# DIOT_SMA_Supply.net
KiCad netlist of a schematic drawn in Altium Designer
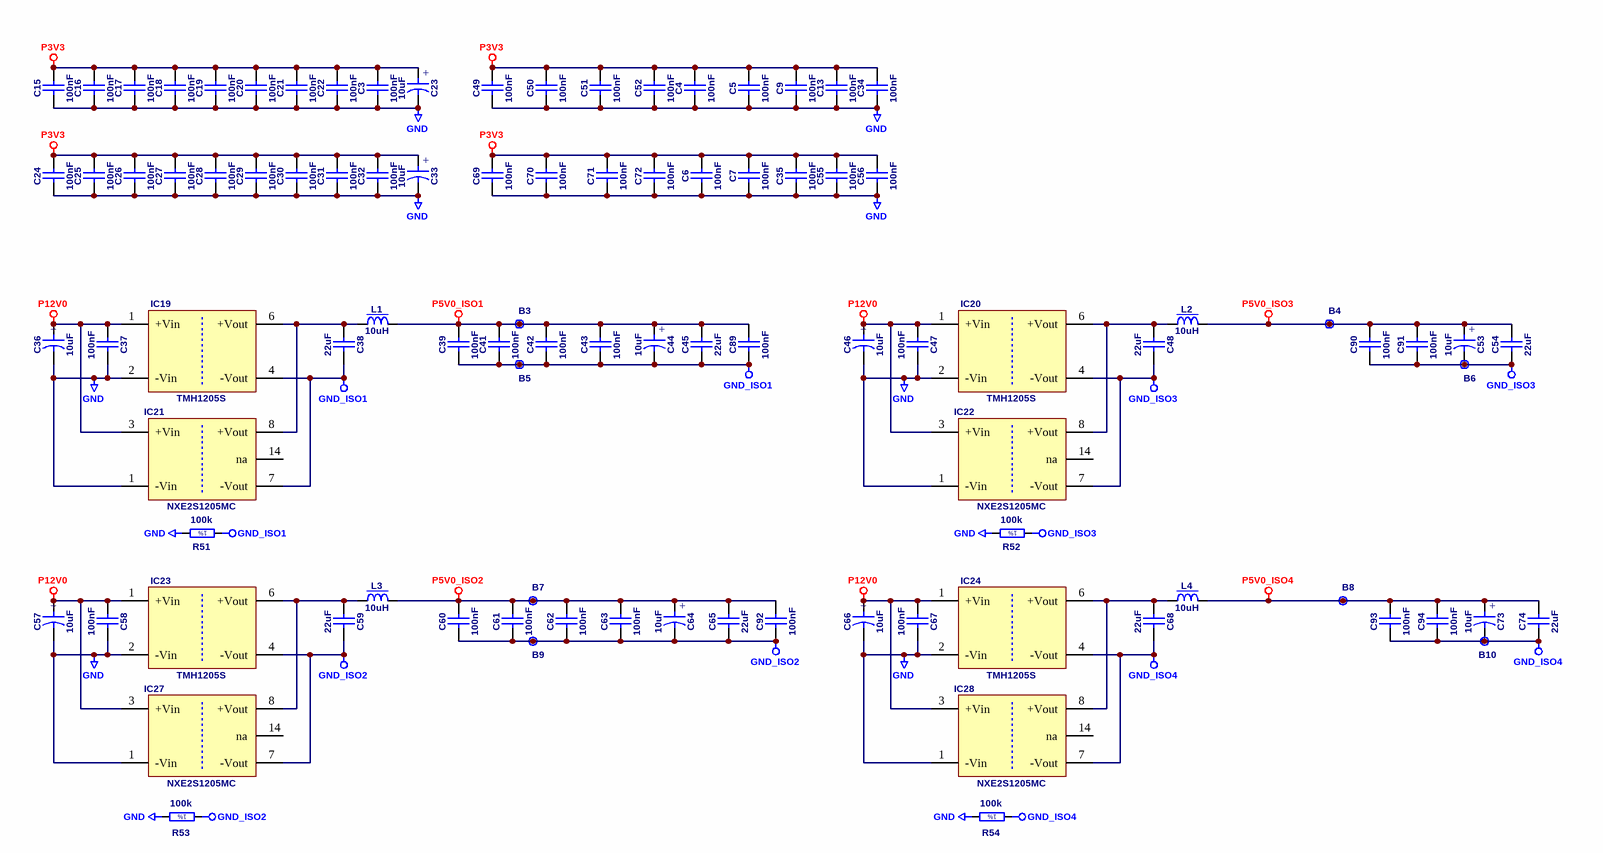
[diagram p0: DIOT_SMA_Supply.SchDoc]

(export (version "E")
  (design (tool "Eeschema 10.0.6"))
  (components
    (comp (ref "B3")
      (value "Plated Hole")
      (footprint "c130h60")
      (description "Single Terminal Socket")
      (fields (field (name "PART NUMBER") "PLATED_HOLE0.6_PAD1.3") (field (name "AUTHOR") "CERN DEM MR"))
      (libsource (lib "Eletro-mechanical") (part "Single Terminal Socket"))
    )
    (comp (ref "B4")
      (value "Plated Hole")
      (footprint "c130h60")
      (description "Single Terminal Socket")
      (fields (field (name "PART NUMBER") "PLATED_HOLE0.6_PAD1.3") (field (name "AUTHOR") "CERN DEM MR"))
      (libsource (lib "Eletro-mechanical") (part "Single Terminal Socket"))
    )
    (comp (ref "B5")
      (value "Plated Hole")
      (footprint "c130h60")
      (description "Single Terminal Socket")
      (fields (field (name "PART NUMBER") "PLATED_HOLE0.6_PAD1.3") (field (name "AUTHOR") "CERN DEM MR"))
      (libsource (lib "Eletro-mechanical") (part "Single Terminal Socket"))
    )
    (comp (ref "B6")
      (value "Plated Hole")
      (footprint "c130h60")
      (description "Single Terminal Socket")
      (fields (field (name "PART NUMBER") "PLATED_HOLE0.6_PAD1.3") (field (name "AUTHOR") "CERN DEM MR"))
      (libsource (lib "Eletro-mechanical") (part "Single Terminal Socket"))
    )
    (comp (ref "B7")
      (value "Plated Hole")
      (footprint "c130h60")
      (description "Single Terminal Socket")
      (fields (field (name "PART NUMBER") "PLATED_HOLE0.6_PAD1.3") (field (name "AUTHOR") "CERN DEM MR"))
      (libsource (lib "Eletro-mechanical") (part "Single Terminal Socket"))
    )
    (comp (ref "B8")
      (value "Plated Hole")
      (footprint "c130h60")
      (description "Single Terminal Socket")
      (fields (field (name "PART NUMBER") "PLATED_HOLE0.6_PAD1.3") (field (name "AUTHOR") "CERN DEM MR"))
      (libsource (lib "Eletro-mechanical") (part "Single Terminal Socket"))
    )
    (comp (ref "B9")
      (value "Plated Hole")
      (footprint "c130h60")
      (description "Single Terminal Socket")
      (fields (field (name "PART NUMBER") "PLATED_HOLE0.6_PAD1.3") (field (name "AUTHOR") "CERN DEM MR"))
      (libsource (lib "Eletro-mechanical") (part "Single Terminal Socket"))
    )
    (comp (ref "B10")
      (value "Plated Hole")
      (footprint "c130h60")
      (description "Single Terminal Socket")
      (fields (field (name "PART NUMBER") "PLATED_HOLE0.6_PAD1.3") (field (name "AUTHOR") "CERN DEM MR"))
      (libsource (lib "Eletro-mechanical") (part "Single Terminal Socket"))
    )
    (comp (ref "C3")
      (value "100nF")
      (footprint "CAPC1005X55N")
      (description "Non-polarised capacitor")
      (fields
        (field (name "PART NUMBER") "CC0402_100NF_16V_10%_X5R")
        (field (name "VOLTAGE") "16V")
        (field (name "AUTHOR") "CERN DEM JLC")
      )
      (libsource (lib "Capacitors") (part "Capacitor - non polarized"))
    )
    (comp (ref "C4")
      (value "100nF")
      (footprint "CAPC1005X55N")
      (description "Non-polarised capacitor")
      (fields
        (field (name "PART NUMBER") "CC0402_100NF_16V_10%_X5R")
        (field (name "VOLTAGE") "16V")
        (field (name "AUTHOR") "CERN DEM JLC")
      )
      (libsource (lib "Capacitors") (part "Capacitor - non polarized"))
    )
    (comp (ref "C5")
      (value "100nF")
      (footprint "CAPC1005X55N")
      (description "Non-polarised capacitor")
      (fields
        (field (name "PART NUMBER") "CC0402_100NF_16V_10%_X5R")
        (field (name "VOLTAGE") "16V")
        (field (name "AUTHOR") "CERN DEM JLC")
      )
      (libsource (lib "Capacitors") (part "Capacitor - non polarized"))
    )
    (comp (ref "C6")
      (value "100nF")
      (footprint "CAPC1005X55N")
      (description "Non-polarised capacitor")
      (fields
        (field (name "PART NUMBER") "CC0402_100NF_16V_10%_X5R")
        (field (name "VOLTAGE") "16V")
        (field (name "AUTHOR") "CERN DEM JLC")
      )
      (libsource (lib "Capacitors") (part "Capacitor - non polarized"))
    )
    (comp (ref "C7")
      (value "100nF")
      (footprint "CAPC1005X55N")
      (description "Non-polarised capacitor")
      (fields
        (field (name "PART NUMBER") "CC0402_100NF_16V_10%_X5R")
        (field (name "VOLTAGE") "16V")
        (field (name "AUTHOR") "CERN DEM JLC")
      )
      (libsource (lib "Capacitors") (part "Capacitor - non polarized"))
    )
    (comp (ref "C9")
      (value "100nF")
      (footprint "CAPC1005X55N")
      (description "Non-polarised capacitor")
      (fields
        (field (name "PART NUMBER") "CC0402_100NF_16V_10%_X5R")
        (field (name "VOLTAGE") "16V")
        (field (name "AUTHOR") "CERN DEM JLC")
      )
      (libsource (lib "Capacitors") (part "Capacitor - non polarized"))
    )
    (comp (ref "C13")
      (value "100nF")
      (footprint "CAPC1005X55N")
      (description "Non-polarised capacitor")
      (fields
        (field (name "PART NUMBER") "CC0402_100NF_16V_10%_X5R")
        (field (name "VOLTAGE") "16V")
        (field (name "AUTHOR") "CERN DEM JLC")
      )
      (libsource (lib "Capacitors") (part "Capacitor - non polarized"))
    )
    (comp (ref "C15")
      (value "100nF")
      (footprint "CAPC1005X55N")
      (description "Non-polarised capacitor")
      (fields
        (field (name "PART NUMBER") "CC0402_100NF_16V_10%_X5R")
        (field (name "VOLTAGE") "16V")
        (field (name "AUTHOR") "CERN DEM JLC")
      )
      (libsource (lib "Capacitors") (part "Capacitor - non polarized"))
    )
    (comp (ref "C16")
      (value "100nF")
      (footprint "CAPC1005X55N")
      (description "Non-polarised capacitor")
      (fields
        (field (name "PART NUMBER") "CC0402_100NF_16V_10%_X5R")
        (field (name "VOLTAGE") "16V")
        (field (name "AUTHOR") "CERN DEM JLC")
      )
      (libsource (lib "Capacitors") (part "Capacitor - non polarized"))
    )
    (comp (ref "C17")
      (value "100nF")
      (footprint "CAPC1005X55N")
      (description "Non-polarised capacitor")
      (fields
        (field (name "PART NUMBER") "CC0402_100NF_16V_10%_X5R")
        (field (name "VOLTAGE") "16V")
        (field (name "AUTHOR") "CERN DEM JLC")
      )
      (libsource (lib "Capacitors") (part "Capacitor - non polarized"))
    )
    (comp (ref "C18")
      (value "100nF")
      (footprint "CAPC1005X55N")
      (description "Non-polarised capacitor")
      (fields
        (field (name "PART NUMBER") "CC0402_100NF_16V_10%_X5R")
        (field (name "VOLTAGE") "16V")
        (field (name "AUTHOR") "CERN DEM JLC")
      )
      (libsource (lib "Capacitors") (part "Capacitor - non polarized"))
    )
    (comp (ref "C19")
      (value "100nF")
      (footprint "CAPC1005X55N")
      (description "Non-polarised capacitor")
      (fields
        (field (name "PART NUMBER") "CC0402_100NF_16V_10%_X5R")
        (field (name "VOLTAGE") "16V")
        (field (name "AUTHOR") "CERN DEM JLC")
      )
      (libsource (lib "Capacitors") (part "Capacitor - non polarized"))
    )
    (comp (ref "C20")
      (value "100nF")
      (footprint "CAPC1005X55N")
      (description "Non-polarised capacitor")
      (fields
        (field (name "PART NUMBER") "CC0402_100NF_16V_10%_X5R")
        (field (name "VOLTAGE") "16V")
        (field (name "AUTHOR") "CERN DEM JLC")
      )
      (libsource (lib "Capacitors") (part "Capacitor - non polarized"))
    )
    (comp (ref "C21")
      (value "100nF")
      (footprint "CAPC1005X55N")
      (description "Non-polarised capacitor")
      (fields
        (field (name "PART NUMBER") "CC0402_100NF_16V_10%_X5R")
        (field (name "VOLTAGE") "16V")
        (field (name "AUTHOR") "CERN DEM JLC")
      )
      (libsource (lib "Capacitors") (part "Capacitor - non polarized"))
    )
    (comp (ref "C22")
      (value "100nF")
      (footprint "CAPC1005X55N")
      (description "Non-polarised capacitor")
      (fields
        (field (name "PART NUMBER") "CC0402_100NF_16V_10%_X5R")
        (field (name "VOLTAGE") "16V")
        (field (name "AUTHOR") "CERN DEM JLC")
      )
      (libsource (lib "Capacitors") (part "Capacitor - non polarized"))
    )
    (comp (ref "C23")
      (value "10uF")
      (footprint "CAPAE430X540N")
      (description "Polarised capacitor")
      (fields
        (field (name "PART NUMBER") "CAE430-540_10UF_16V_20%")
        (field (name "VOLTAGE") "16V")
        (field (name "AUTHOR") "CERN DEM JLC")
      )
      (libsource (lib "Capacitors") (part "Capacitor - polarized"))
    )
    (comp (ref "C24")
      (value "100nF")
      (footprint "CAPC1005X55N")
      (description "Non-polarised capacitor")
      (fields
        (field (name "PART NUMBER") "CC0402_100NF_16V_10%_X5R")
        (field (name "VOLTAGE") "16V")
        (field (name "AUTHOR") "CERN DEM JLC")
      )
      (libsource (lib "Capacitors") (part "Capacitor - non polarized"))
    )
    (comp (ref "C25")
      (value "100nF")
      (footprint "CAPC1005X55N")
      (description "Non-polarised capacitor")
      (fields
        (field (name "PART NUMBER") "CC0402_100NF_16V_10%_X5R")
        (field (name "VOLTAGE") "16V")
        (field (name "AUTHOR") "CERN DEM JLC")
      )
      (libsource (lib "Capacitors") (part "Capacitor - non polarized"))
    )
    (comp (ref "C26")
      (value "100nF")
      (footprint "CAPC1005X55N")
      (description "Non-polarised capacitor")
      (fields
        (field (name "PART NUMBER") "CC0402_100NF_16V_10%_X5R")
        (field (name "VOLTAGE") "16V")
        (field (name "AUTHOR") "CERN DEM JLC")
      )
      (libsource (lib "Capacitors") (part "Capacitor - non polarized"))
    )
    (comp (ref "C27")
      (value "100nF")
      (footprint "CAPC1005X55N")
      (description "Non-polarised capacitor")
      (fields
        (field (name "PART NUMBER") "CC0402_100NF_16V_10%_X5R")
        (field (name "VOLTAGE") "16V")
        (field (name "AUTHOR") "CERN DEM JLC")
      )
      (libsource (lib "Capacitors") (part "Capacitor - non polarized"))
    )
    (comp (ref "C28")
      (value "100nF")
      (footprint "CAPC1005X55N")
      (description "Non-polarised capacitor")
      (fields
        (field (name "PART NUMBER") "CC0402_100NF_16V_10%_X5R")
        (field (name "VOLTAGE") "16V")
        (field (name "AUTHOR") "CERN DEM JLC")
      )
      (libsource (lib "Capacitors") (part "Capacitor - non polarized"))
    )
    (comp (ref "C29")
      (value "100nF")
      (footprint "CAPC1005X55N")
      (description "Non-polarised capacitor")
      (fields
        (field (name "PART NUMBER") "CC0402_100NF_16V_10%_X5R")
        (field (name "VOLTAGE") "16V")
        (field (name "AUTHOR") "CERN DEM JLC")
      )
      (libsource (lib "Capacitors") (part "Capacitor - non polarized"))
    )
    (comp (ref "C30")
      (value "100nF")
      (footprint "CAPC1005X55N")
      (description "Non-polarised capacitor")
      (fields
        (field (name "PART NUMBER") "CC0402_100NF_16V_10%_X5R")
        (field (name "VOLTAGE") "16V")
        (field (name "AUTHOR") "CERN DEM JLC")
      )
      (libsource (lib "Capacitors") (part "Capacitor - non polarized"))
    )
    (comp (ref "C31")
      (value "100nF")
      (footprint "CAPC1005X55N")
      (description "Non-polarised capacitor")
      (fields
        (field (name "PART NUMBER") "CC0402_100NF_16V_10%_X5R")
        (field (name "VOLTAGE") "16V")
        (field (name "AUTHOR") "CERN DEM JLC")
      )
      (libsource (lib "Capacitors") (part "Capacitor - non polarized"))
    )
    (comp (ref "C32")
      (value "100nF")
      (footprint "CAPC1005X55N")
      (description "Non-polarised capacitor")
      (fields
        (field (name "PART NUMBER") "CC0402_100NF_16V_10%_X5R")
        (field (name "VOLTAGE") "16V")
        (field (name "AUTHOR") "CERN DEM JLC")
      )
      (libsource (lib "Capacitors") (part "Capacitor - non polarized"))
    )
    (comp (ref "C33")
      (value "10uF")
      (footprint "CAPAE430X540N")
      (description "Polarised capacitor")
      (fields
        (field (name "PART NUMBER") "CAE430-540_10UF_16V_20%")
        (field (name "VOLTAGE") "16V")
        (field (name "AUTHOR") "CERN DEM JLC")
      )
      (libsource (lib "Capacitors") (part "Capacitor - polarized"))
    )
    (comp (ref "C34")
      (value "100nF")
      (footprint "CAPC1005X55N")
      (description "Non-polarised capacitor")
      (fields
        (field (name "PART NUMBER") "CC0402_100NF_16V_10%_X5R")
        (field (name "VOLTAGE") "16V")
        (field (name "AUTHOR") "CERN DEM JLC")
      )
      (libsource (lib "Capacitors") (part "Capacitor - non polarized"))
    )
    (comp (ref "C35")
      (value "100nF")
      (footprint "CAPC1005X55N")
      (description "Non-polarised capacitor")
      (fields
        (field (name "PART NUMBER") "CC0402_100NF_16V_10%_X5R")
        (field (name "VOLTAGE") "16V")
        (field (name "AUTHOR") "CERN DEM JLC")
      )
      (libsource (lib "Capacitors") (part "Capacitor - non polarized"))
    )
    (comp (ref "C36")
      (value "10uF")
      (footprint "CAPAE430X540N")
      (description "Polarised capacitor")
      (fields
        (field (name "PART NUMBER") "CAE430-540_10UF_16V_20%")
        (field (name "VOLTAGE") "16V")
        (field (name "AUTHOR") "CERN DEM JLC")
      )
      (libsource (lib "") (part "Capacitor - polarized_1"))
    )
    (comp (ref "C37")
      (value "100nF")
      (footprint "CAPC1005X55N")
      (description "Non-polarised capacitor")
      (fields
        (field (name "PART NUMBER") "CC0402_100NF_16V_10%_X5R")
        (field (name "VOLTAGE") "16V")
        (field (name "AUTHOR") "CERN DEM JLC")
      )
      (libsource (lib "Capacitors") (part "Capacitor - non polarized"))
    )
    (comp (ref "C38")
      (value "22uF")
      (footprint "CAPC2012X135N")
      (description "Non-polarised capacitor")
      (fields
        (field (name "PART NUMBER") "CC0805_22UF_16V_10%_X5R")
        (field (name "VOLTAGE") "16V")
        (field (name "AUTHOR") "CERN DEM JLC")
      )
      (libsource (lib "Capacitors") (part "Capacitor - non polarized"))
    )
    (comp (ref "C39")
      (value "100nF")
      (footprint "CAPC1005X55N")
      (description "Non-polarised capacitor")
      (fields
        (field (name "PART NUMBER") "CC0402_100NF_16V_10%_X5R")
        (field (name "VOLTAGE") "16V")
        (field (name "AUTHOR") "CERN DEM JLC")
      )
      (libsource (lib "Capacitors") (part "Capacitor - non polarized"))
    )
    (comp (ref "C41")
      (value "100nF")
      (footprint "CAPC1005X55N")
      (description "Non-polarised capacitor")
      (fields
        (field (name "PART NUMBER") "CC0402_100NF_16V_10%_X5R")
        (field (name "VOLTAGE") "16V")
        (field (name "AUTHOR") "CERN DEM JLC")
      )
      (libsource (lib "Capacitors") (part "Capacitor - non polarized"))
    )
    (comp (ref "C42")
      (value "100nF")
      (footprint "CAPC1005X55N")
      (description "Non-polarised capacitor")
      (fields
        (field (name "PART NUMBER") "CC0402_100NF_16V_10%_X5R")
        (field (name "VOLTAGE") "16V")
        (field (name "AUTHOR") "CERN DEM JLC")
      )
      (libsource (lib "Capacitors") (part "Capacitor - non polarized"))
    )
    (comp (ref "C43")
      (value "100nF")
      (footprint "CAPC1005X55N")
      (description "Non-polarised capacitor")
      (fields
        (field (name "PART NUMBER") "CC0402_100NF_16V_10%_X5R")
        (field (name "VOLTAGE") "16V")
        (field (name "AUTHOR") "CERN DEM JLC")
      )
      (libsource (lib "Capacitors") (part "Capacitor - non polarized"))
    )
    (comp (ref "C44")
      (value "10uF")
      (footprint "CAPAE430X540N")
      (description "Polarised capacitor")
      (fields
        (field (name "PART NUMBER") "CAE430-540_10UF_16V_20%")
        (field (name "VOLTAGE") "16V")
        (field (name "AUTHOR") "CERN DEM JLC")
      )
      (libsource (lib "Capacitors") (part "Capacitor - polarized"))
    )
    (comp (ref "C45")
      (value "22uF")
      (footprint "CAPC2012X135N")
      (description "Non-polarised capacitor")
      (fields
        (field (name "PART NUMBER") "CC0805_22UF_16V_10%_X5R")
        (field (name "VOLTAGE") "16V")
        (field (name "AUTHOR") "CERN DEM JLC")
      )
      (libsource (lib "Capacitors") (part "Capacitor - non polarized"))
    )
    (comp (ref "C46")
      (value "10uF")
      (footprint "CAPAE430X540N")
      (description "Polarised capacitor")
      (fields
        (field (name "PART NUMBER") "CAE430-540_10UF_16V_20%")
        (field (name "VOLTAGE") "16V")
        (field (name "AUTHOR") "CERN DEM JLC")
      )
      (libsource (lib "") (part "Capacitor - polarized_1"))
    )
    (comp (ref "C47")
      (value "100nF")
      (footprint "CAPC1005X55N")
      (description "Non-polarised capacitor")
      (fields
        (field (name "PART NUMBER") "CC0402_100NF_16V_10%_X5R")
        (field (name "VOLTAGE") "16V")
        (field (name "AUTHOR") "CERN DEM JLC")
      )
      (libsource (lib "Capacitors") (part "Capacitor - non polarized"))
    )
    (comp (ref "C48")
      (value "22uF")
      (footprint "CAPC2012X135N")
      (description "Non-polarised capacitor")
      (fields
        (field (name "PART NUMBER") "CC0805_22UF_16V_10%_X5R")
        (field (name "VOLTAGE") "16V")
        (field (name "AUTHOR") "CERN DEM JLC")
      )
      (libsource (lib "Capacitors") (part "Capacitor - non polarized"))
    )
    (comp (ref "C49")
      (value "100nF")
      (footprint "CAPC1005X55N")
      (description "Non-polarised capacitor")
      (fields
        (field (name "PART NUMBER") "CC0402_100NF_16V_10%_X5R")
        (field (name "VOLTAGE") "16V")
        (field (name "AUTHOR") "CERN DEM JLC")
      )
      (libsource (lib "Capacitors") (part "Capacitor - non polarized"))
    )
    (comp (ref "C50")
      (value "100nF")
      (footprint "CAPC1005X55N")
      (description "Non-polarised capacitor")
      (fields
        (field (name "PART NUMBER") "CC0402_100NF_16V_10%_X5R")
        (field (name "VOLTAGE") "16V")
        (field (name "AUTHOR") "CERN DEM JLC")
      )
      (libsource (lib "Capacitors") (part "Capacitor - non polarized"))
    )
    (comp (ref "C51")
      (value "100nF")
      (footprint "CAPC1005X55N")
      (description "Non-polarised capacitor")
      (fields
        (field (name "PART NUMBER") "CC0402_100NF_16V_10%_X5R")
        (field (name "VOLTAGE") "16V")
        (field (name "AUTHOR") "CERN DEM JLC")
      )
      (libsource (lib "Capacitors") (part "Capacitor - non polarized"))
    )
    (comp (ref "C52")
      (value "100nF")
      (footprint "CAPC1005X55N")
      (description "Non-polarised capacitor")
      (fields
        (field (name "PART NUMBER") "CC0402_100NF_16V_10%_X5R")
        (field (name "VOLTAGE") "16V")
        (field (name "AUTHOR") "CERN DEM JLC")
      )
      (libsource (lib "Capacitors") (part "Capacitor - non polarized"))
    )
    (comp (ref "C53")
      (value "10uF")
      (footprint "CAPAE430X540N")
      (description "Polarised capacitor")
      (fields
        (field (name "PART NUMBER") "CAE430-540_10UF_16V_20%")
        (field (name "VOLTAGE") "16V")
        (field (name "AUTHOR") "CERN DEM JLC")
      )
      (libsource (lib "Capacitors") (part "Capacitor - polarized"))
    )
    (comp (ref "C54")
      (value "22uF")
      (footprint "CAPC2012X135N")
      (description "Non-polarised capacitor")
      (fields
        (field (name "PART NUMBER") "CC0805_22UF_16V_10%_X5R")
        (field (name "VOLTAGE") "16V")
        (field (name "AUTHOR") "CERN DEM JLC")
      )
      (libsource (lib "Capacitors") (part "Capacitor - non polarized"))
    )
    (comp (ref "C55")
      (value "100nF")
      (footprint "CAPC1005X55N")
      (description "Non-polarised capacitor")
      (fields
        (field (name "PART NUMBER") "CC0402_100NF_16V_10%_X5R")
        (field (name "VOLTAGE") "16V")
        (field (name "AUTHOR") "CERN DEM JLC")
      )
      (libsource (lib "Capacitors") (part "Capacitor - non polarized"))
    )
    (comp (ref "C56")
      (value "100nF")
      (footprint "CAPC1005X55N")
      (description "Non-polarised capacitor")
      (fields
        (field (name "PART NUMBER") "CC0402_100NF_16V_10%_X5R")
        (field (name "VOLTAGE") "16V")
        (field (name "AUTHOR") "CERN DEM JLC")
      )
      (libsource (lib "Capacitors") (part "Capacitor - non polarized"))
    )
    (comp (ref "C57")
      (value "10uF")
      (footprint "CAPAE430X540N")
      (description "Polarised capacitor")
      (fields
        (field (name "PART NUMBER") "CAE430-540_10UF_16V_20%")
        (field (name "VOLTAGE") "16V")
        (field (name "AUTHOR") "CERN DEM JLC")
      )
      (libsource (lib "") (part "Capacitor - polarized_1"))
    )
    (comp (ref "C58")
      (value "100nF")
      (footprint "CAPC1005X55N")
      (description "Non-polarised capacitor")
      (fields
        (field (name "PART NUMBER") "CC0402_100NF_16V_10%_X5R")
        (field (name "VOLTAGE") "16V")
        (field (name "AUTHOR") "CERN DEM JLC")
      )
      (libsource (lib "Capacitors") (part "Capacitor - non polarized"))
    )
    (comp (ref "C59")
      (value "22uF")
      (footprint "CAPC2012X135N")
      (description "Non-polarised capacitor")
      (fields
        (field (name "PART NUMBER") "CC0805_22UF_16V_10%_X5R")
        (field (name "VOLTAGE") "16V")
        (field (name "AUTHOR") "CERN DEM JLC")
      )
      (libsource (lib "Capacitors") (part "Capacitor - non polarized"))
    )
    (comp (ref "C60")
      (value "100nF")
      (footprint "CAPC1005X55N")
      (description "Non-polarised capacitor")
      (fields
        (field (name "PART NUMBER") "CC0402_100NF_16V_10%_X5R")
        (field (name "VOLTAGE") "16V")
        (field (name "AUTHOR") "CERN DEM JLC")
      )
      (libsource (lib "Capacitors") (part "Capacitor - non polarized"))
    )
    (comp (ref "C61")
      (value "100nF")
      (footprint "CAPC1005X55N")
      (description "Non-polarised capacitor")
      (fields
        (field (name "PART NUMBER") "CC0402_100NF_16V_10%_X5R")
        (field (name "VOLTAGE") "16V")
        (field (name "AUTHOR") "CERN DEM JLC")
      )
      (libsource (lib "Capacitors") (part "Capacitor - non polarized"))
    )
    (comp (ref "C62")
      (value "100nF")
      (footprint "CAPC1005X55N")
      (description "Non-polarised capacitor")
      (fields
        (field (name "PART NUMBER") "CC0402_100NF_16V_10%_X5R")
        (field (name "VOLTAGE") "16V")
        (field (name "AUTHOR") "CERN DEM JLC")
      )
      (libsource (lib "Capacitors") (part "Capacitor - non polarized"))
    )
    (comp (ref "C63")
      (value "100nF")
      (footprint "CAPC1005X55N")
      (description "Non-polarised capacitor")
      (fields
        (field (name "PART NUMBER") "CC0402_100NF_16V_10%_X5R")
        (field (name "VOLTAGE") "16V")
        (field (name "AUTHOR") "CERN DEM JLC")
      )
      (libsource (lib "Capacitors") (part "Capacitor - non polarized"))
    )
    (comp (ref "C64")
      (value "10uF")
      (footprint "CAPAE430X540N")
      (description "Polarised capacitor")
      (fields
        (field (name "PART NUMBER") "CAE430-540_10UF_16V_20%")
        (field (name "VOLTAGE") "16V")
        (field (name "AUTHOR") "CERN DEM JLC")
      )
      (libsource (lib "Capacitors") (part "Capacitor - polarized"))
    )
    (comp (ref "C65")
      (value "22uF")
      (footprint "CAPC2012X135N")
      (description "Non-polarised capacitor")
      (fields
        (field (name "PART NUMBER") "CC0805_22UF_16V_10%_X5R")
        (field (name "VOLTAGE") "16V")
        (field (name "AUTHOR") "CERN DEM JLC")
      )
      (libsource (lib "Capacitors") (part "Capacitor - non polarized"))
    )
    (comp (ref "C66")
      (value "10uF")
      (footprint "CAPAE430X540N")
      (description "Polarised capacitor")
      (fields
        (field (name "PART NUMBER") "CAE430-540_10UF_16V_20%")
        (field (name "VOLTAGE") "16V")
        (field (name "AUTHOR") "CERN DEM JLC")
      )
      (libsource (lib "") (part "Capacitor - polarized_1"))
    )
    (comp (ref "C67")
      (value "100nF")
      (footprint "CAPC1005X55N")
      (description "Non-polarised capacitor")
      (fields
        (field (name "PART NUMBER") "CC0402_100NF_16V_10%_X5R")
        (field (name "VOLTAGE") "16V")
        (field (name "AUTHOR") "CERN DEM JLC")
      )
      (libsource (lib "Capacitors") (part "Capacitor - non polarized"))
    )
    (comp (ref "C68")
      (value "22uF")
      (footprint "CAPC2012X135N")
      (description "Non-polarised capacitor")
      (fields
        (field (name "PART NUMBER") "CC0805_22UF_16V_10%_X5R")
        (field (name "VOLTAGE") "16V")
        (field (name "AUTHOR") "CERN DEM JLC")
      )
      (libsource (lib "Capacitors") (part "Capacitor - non polarized"))
    )
    (comp (ref "C69")
      (value "100nF")
      (footprint "CAPC1005X55N")
      (description "Non-polarised capacitor")
      (fields
        (field (name "PART NUMBER") "CC0402_100NF_16V_10%_X5R")
        (field (name "VOLTAGE") "16V")
        (field (name "AUTHOR") "CERN DEM JLC")
      )
      (libsource (lib "Capacitors") (part "Capacitor - non polarized"))
    )
    (comp (ref "C70")
      (value "100nF")
      (footprint "CAPC1005X55N")
      (description "Non-polarised capacitor")
      (fields
        (field (name "PART NUMBER") "CC0402_100NF_16V_10%_X5R")
        (field (name "VOLTAGE") "16V")
        (field (name "AUTHOR") "CERN DEM JLC")
      )
      (libsource (lib "Capacitors") (part "Capacitor - non polarized"))
    )
    (comp (ref "C71")
      (value "100nF")
      (footprint "CAPC1005X55N")
      (description "Non-polarised capacitor")
      (fields
        (field (name "PART NUMBER") "CC0402_100NF_16V_10%_X5R")
        (field (name "VOLTAGE") "16V")
        (field (name "AUTHOR") "CERN DEM JLC")
      )
      (libsource (lib "Capacitors") (part "Capacitor - non polarized"))
    )
    (comp (ref "C72")
      (value "100nF")
      (footprint "CAPC1005X55N")
      (description "Non-polarised capacitor")
      (fields
        (field (name "PART NUMBER") "CC0402_100NF_16V_10%_X5R")
        (field (name "VOLTAGE") "16V")
        (field (name "AUTHOR") "CERN DEM JLC")
      )
      (libsource (lib "Capacitors") (part "Capacitor - non polarized"))
    )
    (comp (ref "C73")
      (value "10uF")
      (footprint "CAPAE430X540N")
      (description "Polarised capacitor")
      (fields
        (field (name "PART NUMBER") "CAE430-540_10UF_16V_20%")
        (field (name "VOLTAGE") "16V")
        (field (name "AUTHOR") "CERN DEM JLC")
      )
      (libsource (lib "Capacitors") (part "Capacitor - polarized"))
    )
    (comp (ref "C74")
      (value "22uF")
      (footprint "CAPC2012X135N")
      (description "Non-polarised capacitor")
      (fields
        (field (name "PART NUMBER") "CC0805_22UF_16V_10%_X5R")
        (field (name "VOLTAGE") "16V")
        (field (name "AUTHOR") "CERN DEM JLC")
      )
      (libsource (lib "Capacitors") (part "Capacitor - non polarized"))
    )
    (comp (ref "C89")
      (value "100nF")
      (footprint "CAPC1005X55N")
      (description "Non-polarised capacitor")
      (fields
        (field (name "PART NUMBER") "CC0402_100NF_16V_10%_X5R")
        (field (name "VOLTAGE") "16V")
        (field (name "AUTHOR") "CERN DEM JLC")
      )
      (libsource (lib "Capacitors") (part "Capacitor - non polarized"))
    )
    (comp (ref "C90")
      (value "100nF")
      (footprint "CAPC1005X55N")
      (description "Non-polarised capacitor")
      (fields
        (field (name "PART NUMBER") "CC0402_100NF_16V_10%_X5R")
        (field (name "VOLTAGE") "16V")
        (field (name "AUTHOR") "CERN DEM JLC")
      )
      (libsource (lib "Capacitors") (part "Capacitor - non polarized"))
    )
    (comp (ref "C91")
      (value "100nF")
      (footprint "CAPC1005X55N")
      (description "Non-polarised capacitor")
      (fields
        (field (name "PART NUMBER") "CC0402_100NF_16V_10%_X5R")
        (field (name "VOLTAGE") "16V")
        (field (name "AUTHOR") "CERN DEM JLC")
      )
      (libsource (lib "Capacitors") (part "Capacitor - non polarized"))
    )
    (comp (ref "C92")
      (value "100nF")
      (footprint "CAPC1005X55N")
      (description "Non-polarised capacitor")
      (fields
        (field (name "PART NUMBER") "CC0402_100NF_16V_10%_X5R")
        (field (name "VOLTAGE") "16V")
        (field (name "AUTHOR") "CERN DEM JLC")
      )
      (libsource (lib "Capacitors") (part "Capacitor - non polarized"))
    )
    (comp (ref "C93")
      (value "100nF")
      (footprint "CAPC1005X55N")
      (description "Non-polarised capacitor")
      (fields
        (field (name "PART NUMBER") "CC0402_100NF_16V_10%_X5R")
        (field (name "VOLTAGE") "16V")
        (field (name "AUTHOR") "CERN DEM JLC")
      )
      (libsource (lib "Capacitors") (part "Capacitor - non polarized"))
    )
    (comp (ref "C94")
      (value "100nF")
      (footprint "CAPC1005X55N")
      (description "Non-polarised capacitor")
      (fields
        (field (name "PART NUMBER") "CC0402_100NF_16V_10%_X5R")
        (field (name "VOLTAGE") "16V")
        (field (name "AUTHOR") "CERN DEM JLC")
      )
      (libsource (lib "Capacitors") (part "Capacitor - non polarized"))
    )
    (comp (ref "IC19")
      (value "TMH1205S")
      (footprint "DCDC_TRACO_TMA")
      (description "12V ±10% to 5V, Iout (max) 400mA, 2W DC-DC Converter")
      (fields (field (name "MANUFACTURER") "TRACO POWER") (field (name "AUTHOR") "GK"))
      (libsource (lib "Regulators_SMPS") (part "DC/DC_TRACO_TMH1205S"))
    )
    (comp (ref "IC20")
      (value "TMH1205S")
      (footprint "DCDC_TRACO_TMA")
      (description "12V ±10% to 5V, Iout (max) 400mA, 2W DC-DC Converter")
      (fields (field (name "MANUFACTURER") "TRACO POWER") (field (name "AUTHOR") "GK"))
      (libsource (lib "Regulators_SMPS") (part "DC/DC_TRACO_TMH1205S"))
    )
    (comp (ref "IC21")
      (value "NXE2S1205MC")
      (footprint "DCDC_MURATA_NXE2")
      (description "MURATA, NXE2 Serie, Dual Output DCDC Converter")
      (fields (field (name "MANUFACTURER") "MURATA POWER SOLUTIONS") (field (name "AUTHOR") "CERN DEM MR"))
      (libsource (lib "LIBRARY_SCH") (part "DCDC_MURATA_NXE2S1205MC"))
    )
    (comp (ref "IC22")
      (value "NXE2S1205MC")
      (footprint "DCDC_MURATA_NXE2")
      (description "MURATA, NXE2 Serie, Dual Output DCDC Converter")
      (fields (field (name "MANUFACTURER") "MURATA POWER SOLUTIONS") (field (name "AUTHOR") "CERN DEM MR"))
      (libsource (lib "LIBRARY_SCH") (part "DCDC_MURATA_NXE2S1205MC"))
    )
    (comp (ref "IC23")
      (value "TMH1205S")
      (footprint "DCDC_TRACO_TMA")
      (description "12V ±10% to 5V, Iout (max) 400mA, 2W DC-DC Converter")
      (fields (field (name "MANUFACTURER") "TRACO POWER") (field (name "AUTHOR") "GK"))
      (libsource (lib "Regulators_SMPS") (part "DC/DC_TRACO_TMH1205S"))
    )
    (comp (ref "IC24")
      (value "TMH1205S")
      (footprint "DCDC_TRACO_TMA")
      (description "12V ±10% to 5V, Iout (max) 400mA, 2W DC-DC Converter")
      (fields (field (name "MANUFACTURER") "TRACO POWER") (field (name "AUTHOR") "GK"))
      (libsource (lib "Regulators_SMPS") (part "DC/DC_TRACO_TMH1205S"))
    )
    (comp (ref "IC27")
      (value "NXE2S1205MC")
      (footprint "DCDC_MURATA_NXE2")
      (description "MURATA, NXE2 Serie, Dual Output DCDC Converter")
      (fields (field (name "MANUFACTURER") "MURATA POWER SOLUTIONS") (field (name "AUTHOR") "CERN DEM MR"))
      (libsource (lib "LIBRARY_SCH") (part "DCDC_MURATA_NXE2S1205MC"))
    )
    (comp (ref "IC28")
      (value "NXE2S1205MC")
      (footprint "DCDC_MURATA_NXE2")
      (description "MURATA, NXE2 Serie, Dual Output DCDC Converter")
      (fields (field (name "MANUFACTURER") "MURATA POWER SOLUTIONS") (field (name "AUTHOR") "CERN DEM MR"))
      (libsource (lib "LIBRARY_SCH") (part "DCDC_MURATA_NXE2S1205MC"))
    )
    (comp (ref "L1")
      (value "10uH")
      (footprint "IND_MURATA-PS_8400")
      (description "Inductor With Core")
      (fields
        (field (name "PART NUMBER") "IND_10UH_10%_MURATA-PS_8400")
        (field (name "POWER") "950mA")
        (field (name "AUTHOR") "CERN DEM JLC")
      )
      (libsource (lib "Inductors & Transformers") (part "Inductor With Magnetic core"))
    )
    (comp (ref "L2")
      (value "10uH")
      (footprint "IND_MURATA-PS_8400")
      (description "Inductor With Core")
      (fields
        (field (name "PART NUMBER") "IND_10UH_10%_MURATA-PS_8400")
        (field (name "POWER") "950mA")
        (field (name "AUTHOR") "CERN DEM JLC")
      )
      (libsource (lib "Inductors & Transformers") (part "Inductor With Magnetic core"))
    )
    (comp (ref "L3")
      (value "10uH")
      (footprint "IND_MURATA-PS_8400")
      (description "Inductor With Core")
      (fields
        (field (name "PART NUMBER") "IND_10UH_10%_MURATA-PS_8400")
        (field (name "POWER") "950mA")
        (field (name "AUTHOR") "CERN DEM JLC")
      )
      (libsource (lib "Inductors & Transformers") (part "Inductor With Magnetic core"))
    )
    (comp (ref "L4")
      (value "10uH")
      (footprint "IND_MURATA-PS_8400")
      (description "Inductor With Core")
      (fields
        (field (name "PART NUMBER") "IND_10UH_10%_MURATA-PS_8400")
        (field (name "POWER") "950mA")
        (field (name "AUTHOR") "CERN DEM JLC")
      )
      (libsource (lib "Inductors & Transformers") (part "Inductor With Magnetic core"))
    )
    (comp (ref "R51")
      (value "100k")
      (footprint "RESC2012X60N")
      (description "Resistor - 1%")
      (fields
        (field (name "PART NUMBER") "R0805_100K_1%_0.125W_100PPM")
        (field (name "POWER") "0.125W")
        (field (name "AUTHOR") "CERN DEM JLC")
      )
      (libsource (lib "Resistors") (part "Resistor - 1%"))
    )
    (comp (ref "R52")
      (value "100k")
      (footprint "RESC2012X60N")
      (description "Resistor - 1%")
      (fields
        (field (name "PART NUMBER") "R0805_100K_1%_0.125W_100PPM")
        (field (name "POWER") "0.125W")
        (field (name "AUTHOR") "CERN DEM JLC")
      )
      (libsource (lib "Resistors") (part "Resistor - 1%"))
    )
    (comp (ref "R53")
      (value "100k")
      (footprint "RESC2012X60N")
      (description "Resistor - 1%")
      (fields
        (field (name "PART NUMBER") "R0805_100K_1%_0.125W_100PPM")
        (field (name "POWER") "0.125W")
        (field (name "AUTHOR") "CERN DEM JLC")
      )
      (libsource (lib "Resistors") (part "Resistor - 1%"))
    )
    (comp (ref "R54")
      (value "100k")
      (footprint "RESC2012X60N")
      (description "Resistor - 1%")
      (fields
        (field (name "PART NUMBER") "R0805_100K_1%_0.125W_100PPM")
        (field (name "POWER") "0.125W")
        (field (name "AUTHOR") "CERN DEM JLC")
      )
      (libsource (lib "Resistors") (part "Resistor - 1%"))
    )
  )
  (nets
    (net (code "1") (name "GND") (class "Default")
      (node (ref "C13") (pin "1") (pinfunction "1_1") (pintype "passive"))
      (node (ref "C15") (pin "1") (pinfunction "1_1") (pintype "passive"))
      (node (ref "C16") (pin "1") (pinfunction "1_1") (pintype "passive"))
      (node (ref "C17") (pin "1") (pinfunction "1_1") (pintype "passive"))
      (node (ref "C18") (pin "1") (pinfunction "1_1") (pintype "passive"))
      (node (ref "C19") (pin "1") (pinfunction "1_1") (pintype "passive"))
      (node (ref "C20") (pin "1") (pinfunction "1_1") (pintype "passive"))
      (node (ref "C21") (pin "1") (pinfunction "1_1") (pintype "passive"))
      (node (ref "C22") (pin "1") (pinfunction "1_1") (pintype "passive"))
      (node (ref "C23") (pin "2") (pinfunction "2_2") (pintype "passive"))
      (node (ref "C24") (pin "1") (pinfunction "1_1") (pintype "passive"))
      (node (ref "C25") (pin "1") (pinfunction "1_1") (pintype "passive"))
      (node (ref "C26") (pin "1") (pinfunction "1_1") (pintype "passive"))
      (node (ref "C27") (pin "1") (pinfunction "1_1") (pintype "passive"))
      (node (ref "C28") (pin "1") (pinfunction "1_1") (pintype "passive"))
      (node (ref "C29") (pin "1") (pinfunction "1_1") (pintype "passive"))
      (node (ref "C3") (pin "1") (pinfunction "1_1") (pintype "passive"))
      (node (ref "C30") (pin "1") (pinfunction "1_1") (pintype "passive"))
      (node (ref "C31") (pin "1") (pinfunction "1_1") (pintype "passive"))
      (node (ref "C32") (pin "1") (pinfunction "1_1") (pintype "passive"))
      (node (ref "C33") (pin "2") (pinfunction "2_2") (pintype "passive"))
      (node (ref "C34") (pin "1") (pinfunction "1_1") (pintype "passive"))
      (node (ref "C35") (pin "1") (pinfunction "1_1") (pintype "passive"))
      (node (ref "C36") (pin "2") (pinfunction "2_2") (pintype "passive"))
      (node (ref "C37") (pin "1") (pinfunction "1_1") (pintype "passive"))
      (node (ref "C4") (pin "1") (pinfunction "1_1") (pintype "passive"))
      (node (ref "C46") (pin "2") (pinfunction "2_2") (pintype "passive"))
      (node (ref "C47") (pin "1") (pinfunction "1_1") (pintype "passive"))
      (node (ref "C49") (pin "1") (pinfunction "1_1") (pintype "passive"))
      (node (ref "C5") (pin "1") (pinfunction "1_1") (pintype "passive"))
      (node (ref "C50") (pin "1") (pinfunction "1_1") (pintype "passive"))
      (node (ref "C51") (pin "1") (pinfunction "1_1") (pintype "passive"))
      (node (ref "C52") (pin "1") (pinfunction "1_1") (pintype "passive"))
      (node (ref "C55") (pin "1") (pinfunction "1_1") (pintype "passive"))
      (node (ref "C56") (pin "1") (pinfunction "1_1") (pintype "passive"))
      (node (ref "C57") (pin "2") (pinfunction "2_2") (pintype "passive"))
      (node (ref "C58") (pin "1") (pinfunction "1_1") (pintype "passive"))
      (node (ref "C6") (pin "1") (pinfunction "1_1") (pintype "passive"))
      (node (ref "C66") (pin "2") (pinfunction "2_2") (pintype "passive"))
      (node (ref "C67") (pin "1") (pinfunction "1_1") (pintype "passive"))
      (node (ref "C69") (pin "1") (pinfunction "1_1") (pintype "passive"))
      (node (ref "C7") (pin "1") (pinfunction "1_1") (pintype "passive"))
      (node (ref "C70") (pin "1") (pinfunction "1_1") (pintype "passive"))
      (node (ref "C71") (pin "1") (pinfunction "1_1") (pintype "passive"))
      (node (ref "C72") (pin "1") (pinfunction "1_1") (pintype "passive"))
      (node (ref "C9") (pin "1") (pinfunction "1_1") (pintype "passive"))
      (node (ref "IC19") (pin "2") (pinfunction "-Vin_2") (pintype "power_in"))
      (node (ref "IC20") (pin "2") (pinfunction "-Vin_2") (pintype "power_in"))
      (node (ref "IC21") (pin "1") (pinfunction "-Vin_1") (pintype "power_in"))
      (node (ref "IC22") (pin "1") (pinfunction "-Vin_1") (pintype "power_in"))
      (node (ref "IC23") (pin "2") (pinfunction "-Vin_2") (pintype "power_in"))
      (node (ref "IC24") (pin "2") (pinfunction "-Vin_2") (pintype "power_in"))
      (node (ref "IC27") (pin "1") (pinfunction "-Vin_1") (pintype "power_in"))
      (node (ref "IC28") (pin "1") (pinfunction "-Vin_1") (pintype "power_in"))
      (node (ref "R51") (pin "2") (pinfunction "2_2") (pintype "passive"))
      (node (ref "R52") (pin "2") (pinfunction "2_2") (pintype "passive"))
      (node (ref "R53") (pin "2") (pinfunction "2_2") (pintype "passive"))
      (node (ref "R54") (pin "2") (pinfunction "2_2") (pintype "passive"))
    )
    (net (code "2") (name "GND_ISO1") (class "Default")
      (node (ref "B5") (pin "1") (pinfunction "1_1") (pintype "bidirectional"))
      (node (ref "C38") (pin "1") (pinfunction "1_1") (pintype "passive"))
      (node (ref "C39") (pin "1") (pinfunction "1_1") (pintype "passive"))
      (node (ref "C41") (pin "1") (pinfunction "1_1") (pintype "passive"))
      (node (ref "C42") (pin "1") (pinfunction "1_1") (pintype "passive"))
      (node (ref "C43") (pin "1") (pinfunction "1_1") (pintype "passive"))
      (node (ref "C44") (pin "2") (pinfunction "2_2") (pintype "passive"))
      (node (ref "C45") (pin "1") (pinfunction "1_1") (pintype "passive"))
      (node (ref "C89") (pin "1") (pinfunction "1_1") (pintype "passive"))
      (node (ref "IC19") (pin "4") (pinfunction "-Vout_4") (pintype "power_in"))
      (node (ref "IC21") (pin "7") (pinfunction "-Vout_7") (pintype "power_in"))
      (node (ref "R51") (pin "1") (pinfunction "1_1") (pintype "passive"))
    )
    (net (code "3") (name "GND_ISO2") (class "Default")
      (node (ref "B9") (pin "1") (pinfunction "1_1") (pintype "bidirectional"))
      (node (ref "C59") (pin "1") (pinfunction "1_1") (pintype "passive"))
      (node (ref "C60") (pin "1") (pinfunction "1_1") (pintype "passive"))
      (node (ref "C61") (pin "1") (pinfunction "1_1") (pintype "passive"))
      (node (ref "C62") (pin "1") (pinfunction "1_1") (pintype "passive"))
      (node (ref "C63") (pin "1") (pinfunction "1_1") (pintype "passive"))
      (node (ref "C64") (pin "2") (pinfunction "2_2") (pintype "passive"))
      (node (ref "C65") (pin "1") (pinfunction "1_1") (pintype "passive"))
      (node (ref "C92") (pin "1") (pinfunction "1_1") (pintype "passive"))
      (node (ref "IC23") (pin "4") (pinfunction "-Vout_4") (pintype "power_in"))
      (node (ref "IC27") (pin "7") (pinfunction "-Vout_7") (pintype "power_in"))
      (node (ref "R53") (pin "1") (pinfunction "1_1") (pintype "passive"))
    )
    (net (code "4") (name "GND_ISO3") (class "Default")
      (node (ref "B6") (pin "1") (pinfunction "1_1") (pintype "bidirectional"))
      (node (ref "C48") (pin "1") (pinfunction "1_1") (pintype "passive"))
      (node (ref "C53") (pin "2") (pinfunction "2_2") (pintype "passive"))
      (node (ref "C54") (pin "1") (pinfunction "1_1") (pintype "passive"))
      (node (ref "C90") (pin "1") (pinfunction "1_1") (pintype "passive"))
      (node (ref "C91") (pin "1") (pinfunction "1_1") (pintype "passive"))
      (node (ref "IC20") (pin "4") (pinfunction "-Vout_4") (pintype "power_in"))
      (node (ref "IC22") (pin "7") (pinfunction "-Vout_7") (pintype "power_in"))
      (node (ref "R52") (pin "1") (pinfunction "1_1") (pintype "passive"))
    )
    (net (code "5") (name "GND_ISO4") (class "Default")
      (node (ref "B10") (pin "1") (pinfunction "1_1") (pintype "bidirectional"))
      (node (ref "C68") (pin "1") (pinfunction "1_1") (pintype "passive"))
      (node (ref "C73") (pin "2") (pinfunction "2_2") (pintype "passive"))
      (node (ref "C74") (pin "1") (pinfunction "1_1") (pintype "passive"))
      (node (ref "C93") (pin "1") (pinfunction "1_1") (pintype "passive"))
      (node (ref "C94") (pin "1") (pinfunction "1_1") (pintype "passive"))
      (node (ref "IC24") (pin "4") (pinfunction "-Vout_4") (pintype "power_in"))
      (node (ref "IC28") (pin "7") (pinfunction "-Vout_7") (pintype "power_in"))
      (node (ref "R54") (pin "1") (pinfunction "1_1") (pintype "passive"))
    )
    (net (code "6") (name "Net-(IC19-+Vout)") (class "Default")
      (node (ref "C38") (pin "2") (pinfunction "2_2") (pintype "passive"))
      (node (ref "IC19") (pin "6") (pinfunction "+Vout_6") (pintype "power_in"))
      (node (ref "IC21") (pin "8") (pinfunction "+Vout_8") (pintype "power_in"))
      (node (ref "L1") (pin "2") (pinfunction "2_2") (pintype "passive"))
    )
    (net (code "7") (name "Net-(IC20-+Vout)") (class "Default")
      (node (ref "C48") (pin "2") (pinfunction "2_2") (pintype "passive"))
      (node (ref "IC20") (pin "6") (pinfunction "+Vout_6") (pintype "power_in"))
      (node (ref "IC22") (pin "8") (pinfunction "+Vout_8") (pintype "power_in"))
      (node (ref "L2") (pin "2") (pinfunction "2_2") (pintype "passive"))
    )
    (net (code "8") (name "Net-(IC23-+Vout)") (class "Default")
      (node (ref "C59") (pin "2") (pinfunction "2_2") (pintype "passive"))
      (node (ref "IC23") (pin "6") (pinfunction "+Vout_6") (pintype "power_in"))
      (node (ref "IC27") (pin "8") (pinfunction "+Vout_8") (pintype "power_in"))
      (node (ref "L3") (pin "2") (pinfunction "2_2") (pintype "passive"))
    )
    (net (code "9") (name "Net-(IC24-+Vout)") (class "Default")
      (node (ref "C68") (pin "2") (pinfunction "2_2") (pintype "passive"))
      (node (ref "IC24") (pin "6") (pinfunction "+Vout_6") (pintype "power_in"))
      (node (ref "IC28") (pin "8") (pinfunction "+Vout_8") (pintype "power_in"))
      (node (ref "L4") (pin "2") (pinfunction "2_2") (pintype "passive"))
    )
    (net (code "10") (name "P3V3") (class "Default")
      (node (ref "C13") (pin "2") (pinfunction "2_2") (pintype "passive"))
      (node (ref "C15") (pin "2") (pinfunction "2_2") (pintype "passive"))
      (node (ref "C16") (pin "2") (pinfunction "2_2") (pintype "passive"))
      (node (ref "C17") (pin "2") (pinfunction "2_2") (pintype "passive"))
      (node (ref "C18") (pin "2") (pinfunction "2_2") (pintype "passive"))
      (node (ref "C19") (pin "2") (pinfunction "2_2") (pintype "passive"))
      (node (ref "C20") (pin "2") (pinfunction "2_2") (pintype "passive"))
      (node (ref "C21") (pin "2") (pinfunction "2_2") (pintype "passive"))
      (node (ref "C22") (pin "2") (pinfunction "2_2") (pintype "passive"))
      (node (ref "C23") (pin "1") (pinfunction "1_1") (pintype "passive"))
      (node (ref "C24") (pin "2") (pinfunction "2_2") (pintype "passive"))
      (node (ref "C25") (pin "2") (pinfunction "2_2") (pintype "passive"))
      (node (ref "C26") (pin "2") (pinfunction "2_2") (pintype "passive"))
      (node (ref "C27") (pin "2") (pinfunction "2_2") (pintype "passive"))
      (node (ref "C28") (pin "2") (pinfunction "2_2") (pintype "passive"))
      (node (ref "C29") (pin "2") (pinfunction "2_2") (pintype "passive"))
      (node (ref "C3") (pin "2") (pinfunction "2_2") (pintype "passive"))
      (node (ref "C30") (pin "2") (pinfunction "2_2") (pintype "passive"))
      (node (ref "C31") (pin "2") (pinfunction "2_2") (pintype "passive"))
      (node (ref "C32") (pin "2") (pinfunction "2_2") (pintype "passive"))
      (node (ref "C33") (pin "1") (pinfunction "1_1") (pintype "passive"))
      (node (ref "C34") (pin "2") (pinfunction "2_2") (pintype "passive"))
      (node (ref "C35") (pin "2") (pinfunction "2_2") (pintype "passive"))
      (node (ref "C4") (pin "2") (pinfunction "2_2") (pintype "passive"))
      (node (ref "C49") (pin "2") (pinfunction "2_2") (pintype "passive"))
      (node (ref "C5") (pin "2") (pinfunction "2_2") (pintype "passive"))
      (node (ref "C50") (pin "2") (pinfunction "2_2") (pintype "passive"))
      (node (ref "C51") (pin "2") (pinfunction "2_2") (pintype "passive"))
      (node (ref "C52") (pin "2") (pinfunction "2_2") (pintype "passive"))
      (node (ref "C55") (pin "2") (pinfunction "2_2") (pintype "passive"))
      (node (ref "C56") (pin "2") (pinfunction "2_2") (pintype "passive"))
      (node (ref "C6") (pin "2") (pinfunction "2_2") (pintype "passive"))
      (node (ref "C69") (pin "2") (pinfunction "2_2") (pintype "passive"))
      (node (ref "C7") (pin "2") (pinfunction "2_2") (pintype "passive"))
      (node (ref "C70") (pin "2") (pinfunction "2_2") (pintype "passive"))
      (node (ref "C71") (pin "2") (pinfunction "2_2") (pintype "passive"))
      (node (ref "C72") (pin "2") (pinfunction "2_2") (pintype "passive"))
      (node (ref "C9") (pin "2") (pinfunction "2_2") (pintype "passive"))
    )
    (net (code "11") (name "P5V0_ISO1") (class "Default")
      (node (ref "B3") (pin "1") (pinfunction "1_1") (pintype "bidirectional"))
      (node (ref "C39") (pin "2") (pinfunction "2_2") (pintype "passive"))
      (node (ref "C41") (pin "2") (pinfunction "2_2") (pintype "passive"))
      (node (ref "C42") (pin "2") (pinfunction "2_2") (pintype "passive"))
      (node (ref "C43") (pin "2") (pinfunction "2_2") (pintype "passive"))
      (node (ref "C44") (pin "1") (pinfunction "1_1") (pintype "passive"))
      (node (ref "C45") (pin "2") (pinfunction "2_2") (pintype "passive"))
      (node (ref "C89") (pin "2") (pinfunction "2_2") (pintype "passive"))
      (node (ref "L1") (pin "1") (pinfunction "1_1") (pintype "passive"))
    )
    (net (code "12") (name "P5V0_ISO2") (class "Default")
      (node (ref "B7") (pin "1") (pinfunction "1_1") (pintype "bidirectional"))
      (node (ref "C60") (pin "2") (pinfunction "2_2") (pintype "passive"))
      (node (ref "C61") (pin "2") (pinfunction "2_2") (pintype "passive"))
      (node (ref "C62") (pin "2") (pinfunction "2_2") (pintype "passive"))
      (node (ref "C63") (pin "2") (pinfunction "2_2") (pintype "passive"))
      (node (ref "C64") (pin "1") (pinfunction "1_1") (pintype "passive"))
      (node (ref "C65") (pin "2") (pinfunction "2_2") (pintype "passive"))
      (node (ref "C92") (pin "2") (pinfunction "2_2") (pintype "passive"))
      (node (ref "L3") (pin "1") (pinfunction "1_1") (pintype "passive"))
    )
    (net (code "13") (name "P5V0_ISO3") (class "Default")
      (node (ref "B4") (pin "1") (pinfunction "1_1") (pintype "bidirectional"))
      (node (ref "C53") (pin "1") (pinfunction "1_1") (pintype "passive"))
      (node (ref "C54") (pin "2") (pinfunction "2_2") (pintype "passive"))
      (node (ref "C90") (pin "2") (pinfunction "2_2") (pintype "passive"))
      (node (ref "C91") (pin "2") (pinfunction "2_2") (pintype "passive"))
      (node (ref "L2") (pin "1") (pinfunction "1_1") (pintype "passive"))
    )
    (net (code "14") (name "P5V0_ISO4") (class "Default")
      (node (ref "B8") (pin "1") (pinfunction "1_1") (pintype "bidirectional"))
      (node (ref "C73") (pin "1") (pinfunction "1_1") (pintype "passive"))
      (node (ref "C74") (pin "2") (pinfunction "2_2") (pintype "passive"))
      (node (ref "C93") (pin "2") (pinfunction "2_2") (pintype "passive"))
      (node (ref "C94") (pin "2") (pinfunction "2_2") (pintype "passive"))
      (node (ref "L4") (pin "1") (pinfunction "1_1") (pintype "passive"))
    )
    (net (code "15") (name "P12V0") (class "Default")
      (node (ref "C36") (pin "1") (pinfunction "1_1") (pintype "passive"))
      (node (ref "C37") (pin "2") (pinfunction "2_2") (pintype "passive"))
      (node (ref "C46") (pin "1") (pinfunction "1_1") (pintype "passive"))
      (node (ref "C47") (pin "2") (pinfunction "2_2") (pintype "passive"))
      (node (ref "C57") (pin "1") (pinfunction "1_1") (pintype "passive"))
      (node (ref "C58") (pin "2") (pinfunction "2_2") (pintype "passive"))
      (node (ref "C66") (pin "1") (pinfunction "1_1") (pintype "passive"))
      (node (ref "C67") (pin "2") (pinfunction "2_2") (pintype "passive"))
      (node (ref "IC19") (pin "1") (pinfunction "+Vin_1") (pintype "power_in"))
      (node (ref "IC20") (pin "1") (pinfunction "+Vin_1") (pintype "power_in"))
      (node (ref "IC21") (pin "3") (pinfunction "+Vin_3") (pintype "power_in"))
      (node (ref "IC22") (pin "3") (pinfunction "+Vin_3") (pintype "power_in"))
      (node (ref "IC23") (pin "1") (pinfunction "+Vin_1") (pintype "power_in"))
      (node (ref "IC24") (pin "1") (pinfunction "+Vin_1") (pintype "power_in"))
      (node (ref "IC27") (pin "3") (pinfunction "+Vin_3") (pintype "power_in"))
      (node (ref "IC28") (pin "3") (pinfunction "+Vin_3") (pintype "power_in"))
    )
    (net (code "16") (name "unconnected-(IC21-na-Pad14)") (class "Default")
      (node (ref "IC21") (pin "14") (pinfunction "na_14") (pintype "passive"))
    )
    (net (code "17") (name "unconnected-(IC22-na-Pad14)") (class "Default")
      (node (ref "IC22") (pin "14") (pinfunction "na_14") (pintype "passive"))
    )
    (net (code "18") (name "unconnected-(IC27-na-Pad14)") (class "Default")
      (node (ref "IC27") (pin "14") (pinfunction "na_14") (pintype "passive"))
    )
    (net (code "19") (name "unconnected-(IC28-na-Pad14)") (class "Default")
      (node (ref "IC28") (pin "14") (pinfunction "na_14") (pintype "passive"))
    )
  )
)
